# Regulator.net
KiCad netlist of a schematic drawn in Altium Designer
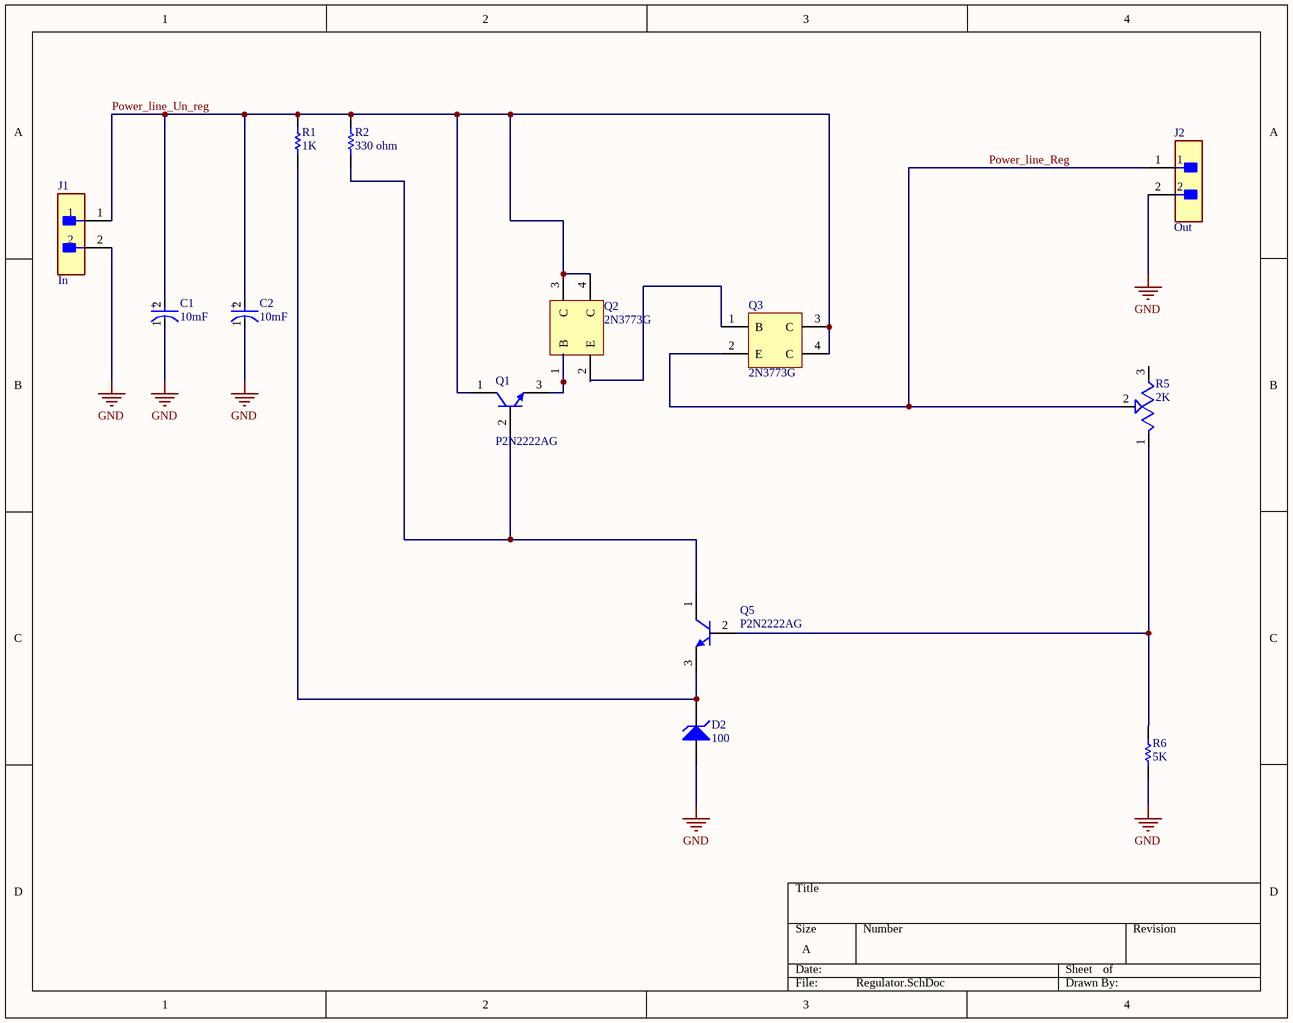
[diagram p0: Regulator.SchDoc]

(export (version "E")
  (design (tool "Eeschema 10.0.6"))
  (components
    (comp (ref "C1")
      (value "10mF")
      (footprint "FP-RAD-TH-D_16_0_5-L_25_2-MFG")
      (description "Aluminum Electrolytic Capacitors (Radial Lead Type) AEC-Q200 Qualified 10000uF ±20% 10V")
      (fields (field (name "TOLERANCE") "20%") (field (name "VOLTAGE") "10V"))
      (libsource (lib "Altium Content Vault") (part "203bc49f2ac43e59fd269a8c329ed05"))
    )
    (comp (ref "C2")
      (value "10mF")
      (footprint "FP-RAD-TH-D_16_0_5-L_25_2-MFG")
      (description "Aluminum Electrolytic Capacitors (Radial Lead Type) AEC-Q200 Qualified 10000uF ±20% 10V")
      (fields (field (name "TOLERANCE") "20%") (field (name "VOLTAGE") "10V"))
      (libsource (lib "Altium Content Vault") (part "203bc49f2ac43e59fd269a8c329ed05"))
    )
    (comp (ref "D2")
      (value "Zener Diode")
      (fields (field (name "BV") "100"))
      (libsource (lib "Simulation Generic Components") (part "Zener Diode"))
    )
    (comp (ref "J1")
      (value "In")
      (footprint "FP-B2B-XH-A_LF_SN-MFG")
      (description "CONN HEADER VERT 2POS 2.5MM")
      (libsource (lib "") (part "3bc925449376181038e59eaffc5286c_1"))
    )
    (comp (ref "J2")
      (value "Out")
      (footprint "FP-B2B-XH-A_LF_SN-MFG")
      (description "CONN HEADER VERT 2POS 2.5MM")
      (libsource (lib "Altium Content Vault") (part "3bc925449376181038e59eaffc5286c"))
    )
    (comp (ref "Q1")
      (value "P2N2222AG")
      (footprint "ONSC-TO-92-3-29-11")
      (description "Amplifier Transistor, NPN Silicon, 3-Pin TO-92, Pb-Free, Bulk Box")
      (fields (field (name "MANUFACTURER") "On Semiconductor"))
      (libsource (lib "Altium Content Vault") (part "ONSC-NPN-C1B2E3-3"))
    )
    (comp (ref "Q2")
      (value "2N3773G")
      (footprint "ONSC-TO-204-3-1-07")
      (description "NPN Power Transistor, 3-Pin TO-204, Pb-Free, Tray")
      (fields (field (name "MANUFACTURER") "On Semiconductor"))
      (libsource (lib "Altium Content Vault") (part "ONSC-NPN-B1E2C34-3_A"))
    )
    (comp (ref "Q3")
      (value "2N3773G")
      (footprint "ONSC-TO-204-3-1-07")
      (description "NPN Power Transistor, 3-Pin TO-204, Pb-Free, Tray")
      (fields (field (name "MANUFACTURER") "On Semiconductor"))
      (libsource (lib "") (part "ONSC-NPN-B1E2C34-3_A_1"))
    )
    (comp (ref "Q5")
      (value "P2N2222AG")
      (footprint "ONSC-TO-92-3-29-11")
      (description "Amplifier Transistor, NPN Silicon, 3-Pin TO-92, Pb-Free, Bulk Box")
      (fields (field (name "MANUFACTURER") "On Semiconductor"))
      (libsource (lib "Altium Content Vault") (part "ONSC-NPN-C1B2E3-3"))
    )
    (comp (ref "R1")
      (value "1K")
      (footprint "OMTE-WLA-2_V2")
      (description "Miniature Wirewound Current Sense, 0.02 Ohm +/-1%, 0.5 W, 2-Pin THD, RoHS, 25pc Pack")
      (fields (field (name "PARTNUMBER") "WLAR020FE") (field (name "MANUFACTURER") "Ohmite"))
      (libsource (lib "Altium Content Vault") (part "OMTE-RES-2"))
    )
    (comp (ref "R2")
      (value "330 ohm")
      (footprint "OMTE-WLA-2_V2")
      (description "Miniature Wirewound Current Sense, 0.02 Ohm +/-1%, 0.5 W, 2-Pin THD, RoHS, 25pc Pack")
      (fields (field (name "PARTNUMBER") "WLAR020FE") (field (name "MANUFACTURER") "Ohmite"))
      (libsource (lib "Altium Content Vault") (part "OMTE-RES-2"))
    )
    (comp (ref "R5")
      (value "2K")
      (footprint "TRIM_3306F-1-104")
      (description "100 kOhms 0.2W, 1/5W PC Pins Through Hole Trimmer Potentiometer Cermet 1 Turn Top Adjustment")
      (fields (field (name "MP") "3306F-1-104") (field (name "MF") "Bourns"))
      (libsource (lib "Schlib1") (part "3306F-1-104"))
    )
    (comp (ref "R6")
      (value "5K")
      (footprint "OMTE-WLA-2_V2")
      (description "Miniature Wirewound Current Sense, 0.02 Ohm +/-1%, 0.5 W, 2-Pin THD, RoHS, 25pc Pack")
      (fields (field (name "PARTNUMBER") "WLAR020FE") (field (name "MANUFACTURER") "Ohmite"))
      (libsource (lib "Altium Content Vault") (part "OMTE-RES-2"))
    )
  )
  (nets
    (net (code "1") (name "/Power_line_Reg") (class "Default")
      (node (ref "J2") (pin "1") (pinfunction "1_1") (pintype "passive"))
      (node (ref "Q3") (pin "2") (pinfunction "E_2") (pintype "passive"))
      (node (ref "R5") (pin "2") (pinfunction "W_2") (pintype "passive"))
    )
    (net (code "2") (name "/Power_line_Un_reg") (class "Default")
      (node (ref "C1") (pin "2") (pinfunction "A_2") (pintype "passive"))
      (node (ref "C2") (pin "2") (pinfunction "A_2") (pintype "passive"))
      (node (ref "J1") (pin "1") (pinfunction "1_1") (pintype "passive"))
      (node (ref "Q1") (pin "1") (pinfunction "C_1") (pintype "passive"))
      (node (ref "Q2") (pin "3") (pinfunction "C_3") (pintype "passive"))
      (node (ref "Q2") (pin "4") (pinfunction "C_4") (pintype "passive"))
      (node (ref "Q3") (pin "3") (pinfunction "C_3") (pintype "passive"))
      (node (ref "Q3") (pin "4") (pinfunction "C_4") (pintype "passive"))
      (node (ref "R1") (pin "2") (pinfunction "2_2") (pintype "passive"))
      (node (ref "R2") (pin "2") (pinfunction "2_2") (pintype "passive"))
    )
    (net (code "3") (name "GND") (class "Default")
      (node (ref "C1") (pin "1") (pinfunction "C_1") (pintype "passive"))
      (node (ref "C2") (pin "1") (pinfunction "C_1") (pintype "passive"))
      (node (ref "D2") (pin "1") (pinfunction "A_1") (pintype "passive"))
      (node (ref "J1") (pin "2") (pinfunction "2_2") (pintype "passive"))
      (node (ref "J2") (pin "2") (pinfunction "2_2") (pintype "passive"))
      (node (ref "R6") (pin "1") (pinfunction "1_1") (pintype "passive"))
    )
    (net (code "4") (name "Net-(D2-K)") (class "Default")
      (node (ref "D2") (pin "2") (pinfunction "K_2") (pintype "passive"))
      (node (ref "Q5") (pin "3") (pinfunction "E_3") (pintype "passive"))
      (node (ref "R1") (pin "1") (pinfunction "1_1") (pintype "passive"))
    )
    (net (code "5") (name "Net-(Q1-B)") (class "Default")
      (node (ref "Q1") (pin "2") (pinfunction "B_2") (pintype "passive"))
      (node (ref "Q5") (pin "1") (pinfunction "C_1") (pintype "passive"))
      (node (ref "R2") (pin "1") (pinfunction "1_1") (pintype "passive"))
    )
    (net (code "6") (name "Net-(Q1-E)") (class "Default")
      (node (ref "Q1") (pin "3") (pinfunction "E_3") (pintype "passive"))
      (node (ref "Q2") (pin "1") (pinfunction "B_1") (pintype "passive"))
    )
    (net (code "7") (name "Net-(Q2-E)") (class "Default")
      (node (ref "Q2") (pin "2") (pinfunction "E_2") (pintype "passive"))
      (node (ref "Q3") (pin "1") (pinfunction "B_1") (pintype "passive"))
    )
    (net (code "8") (name "Net-(Q5-B)") (class "Default")
      (node (ref "Q5") (pin "2") (pinfunction "B_2") (pintype "passive"))
      (node (ref "R5") (pin "1") (pinfunction "CCW_1") (pintype "passive"))
      (node (ref "R6") (pin "2") (pinfunction "2_2") (pintype "passive"))
    )
    (net (code "9") (name "unconnected-(R5-CW-Pad3)") (class "Default")
      (node (ref "R5") (pin "3") (pinfunction "CW_3") (pintype "passive"))
    )
  )
)
